# NG9093_EEPROM.net
KiCad netlist of a schematic drawn in Altium Designer
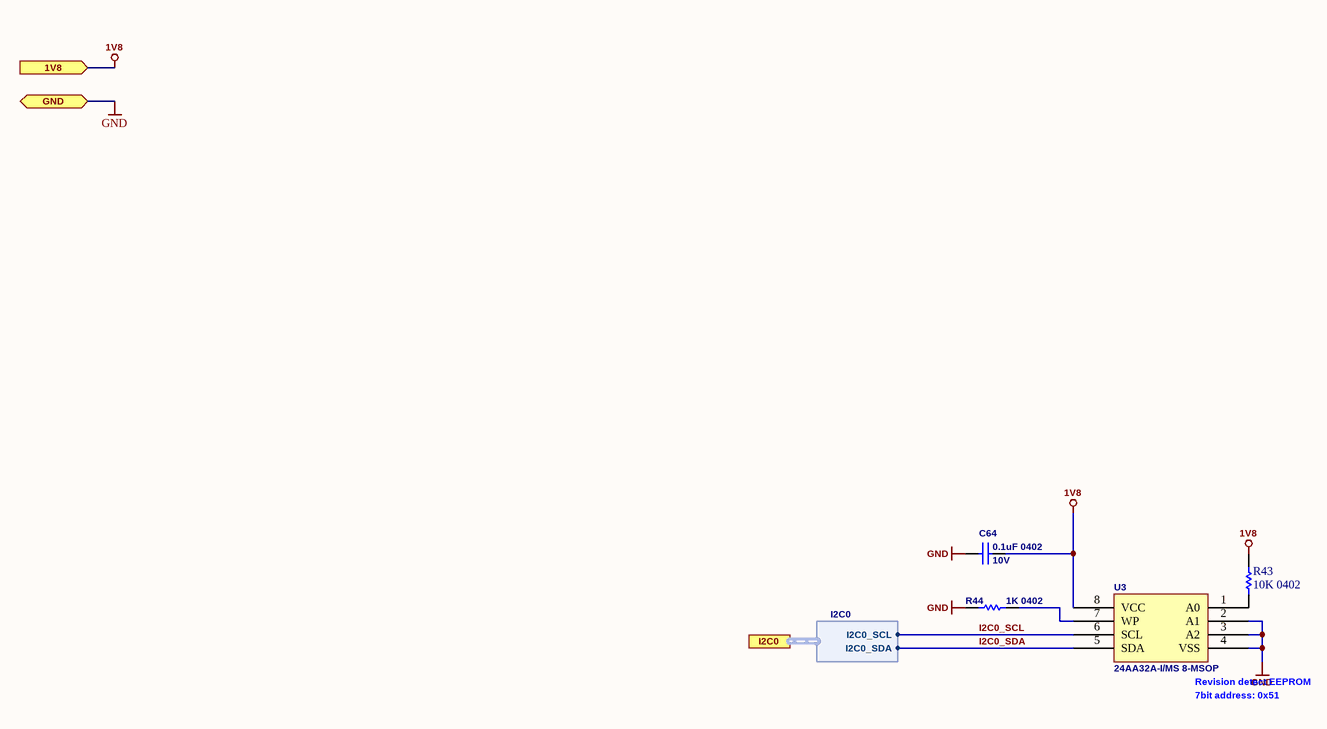
[diagram p0: NG9093_EEPROM.SchDoc]

(export (version "E")
  (design (tool "Eeschema 10.0.6"))
  (components
    (comp (ref "C64")
      (value "0.1uF 0402")
      (footprint "CAP_Altium_Vault_Generic:CAPC0402(1005)70_L")
      (description "CAP CER 0.1UF 10V X7R 0402 5%")
      (fields (field (name "TOLERANCE") "5%") (field (name "VOLTAGE RATING") "10V"))
      (libsource (lib "LuxonisMaster") (part "GRM155R71A104JA01D"))
    )
    (comp (ref "R43")
      (value "10K 0402")
      (footprint "RES_Altium_Vault_Generic:RESC0402(1005)_N")
      (fields (field (name "TOLERANCE") "1%"))
      (libsource (lib "LuxonisMaster") (part "RC0402FR-1310KL"))
    )
    (comp (ref "R44")
      (value "1K 0402")
      (footprint "RES_Altium_Vault_Generic:RESC0402(1005)_L")
      (fields (field (name "TOLERANCE") "1%"))
      (libsource (lib "LuxonisMaster") (part "RC0402FR-071KL"))
    )
    (comp (ref "U3")
      (value "24AA32A-I/MS 8-MSOP")
      (footprint "LuxonisMaster:24AA32A-I/MS")
      (description "IC EEPROM 32K I2C 400KHZ 8MSOP Memory IC 32Kb (4K x 8) I²C 400kHz 900ns 8-MSOP")
      (libsource (lib "LuxonisMaster") (part "24AA32A-I/MS"))
    )
  )
  (nets
    (net (code "2") (name "/I2C0_SCL") (class "Default")
      (node (ref "U3") (pin "6") (pinfunction "SCL_6") (pintype "passive"))
    )
    (net (code "3") (name "/I2C0_SDA") (class "Default")
      (node (ref "U3") (pin "5") (pinfunction "SDA_5") (pintype "passive"))
    )
    (net (code "5") (name "1V8") (class "Default")
      (node (ref "C64") (pin "2") (pinfunction "2_2") (pintype "passive"))
      (node (ref "R43") (pin "2") (pinfunction "2_2") (pintype "passive"))
      (node (ref "U3") (pin "8") (pinfunction "VCC_8") (pintype "passive"))
    )
    (net (code "6") (name "GND") (class "Default")
      (node (ref "C64") (pin "1") (pinfunction "1_1") (pintype "passive"))
      (node (ref "R44") (pin "1") (pinfunction "1_1") (pintype "passive"))
      (node (ref "U3") (pin "2") (pinfunction "A1_2") (pintype "passive"))
      (node (ref "U3") (pin "3") (pinfunction "A2_3") (pintype "passive"))
      (node (ref "U3") (pin "4") (pinfunction "VSS_4") (pintype "passive"))
    )
    (net (code "7") (name "Net-(U3-A0)") (class "Default")
      (node (ref "R43") (pin "1") (pinfunction "1_1") (pintype "passive"))
      (node (ref "U3") (pin "1") (pinfunction "A0_1") (pintype "passive"))
    )
    (net (code "8") (name "Net-(U3-WP)") (class "Default")
      (node (ref "R44") (pin "2") (pinfunction "2_2") (pintype "passive"))
      (node (ref "U3") (pin "7") (pinfunction "WP_7") (pintype "passive"))
    )
  )
)
